# Key_Reset.net
KiCad netlist of a schematic drawn in Altium Designer
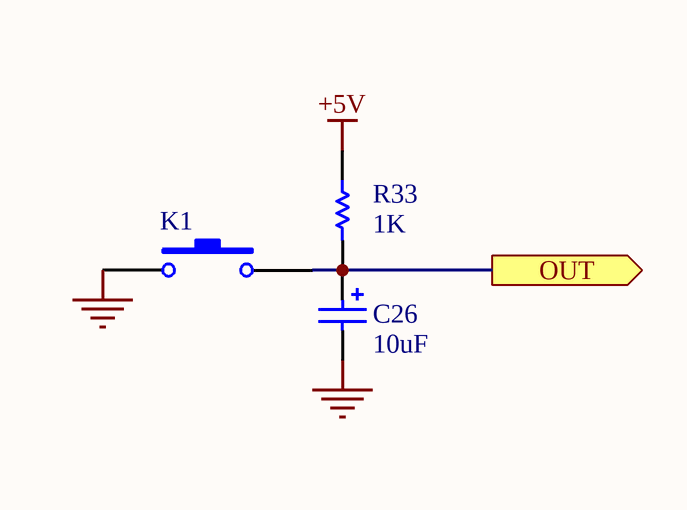
[diagram p0: Key_Reset.SchDoc]

(export (version "E")
  (design (tool "Eeschema 10.0.6"))
  (components
    (comp (ref "C26")
      (value "10uF")
      (footprint "CAPPR2.5-6.3x5")
      (description "Polarized Capacitor (Radial)")
      (fields
        (field (name "MANUFACTURER") "Generic Components")
        (field (name "Comment") "Cap Pol1")
        (field (name "PUBLISHER") "Altium Limited")
      )
      (libsource (lib "Miscellaneous Devices") (part "Cap Pol1"))
    )
    (comp (ref "K1")
      (value "SW-PB")
      (footprint "SPST-2_2")
      (description "Switch")
      (fields (field (name "MANUFACTURER") "Generic Components") (field (name "PUBLISHER") "Altium Limited"))
      (libsource (lib "Miscellaneous Devices") (part "SW-PB"))
    )
    (comp (ref "R33")
      (value "1K")
      (footprint "AXIAL-0.4")
      (description "Resistor")
      (fields
        (field (name "MANUFACTURER") "Generic Components")
        (field (name "Comment") "Res1")
        (field (name "PUBLISHER") "Altium Limited")
      )
      (libsource (lib "Miscellaneous Devices") (part "Res1"))
    )
  )
  (nets
    (net (code "1") (name "+5V") (class "Default")
      (node (ref "R33") (pin "1") (pinfunction "1_1") (pintype "passive"))
    )
    (net (code "2") (name "/OUT") (class "Default")
      (node (ref "C26") (pin "1") (pinfunction "1_1") (pintype "passive"))
      (node (ref "K1") (pin "2") (pinfunction "2_2") (pintype "passive"))
      (node (ref "R33") (pin "2") (pinfunction "2_2") (pintype "passive"))
    )
    (net (code "3") (name "GND") (class "Default")
      (node (ref "C26") (pin "2") (pinfunction "2_2") (pintype "passive"))
      (node (ref "K1") (pin "1") (pinfunction "1_1") (pintype "passive"))
    )
  )
)
